# FISHFEEDER.net
KiCad netlist of a schematic drawn in EAGLE
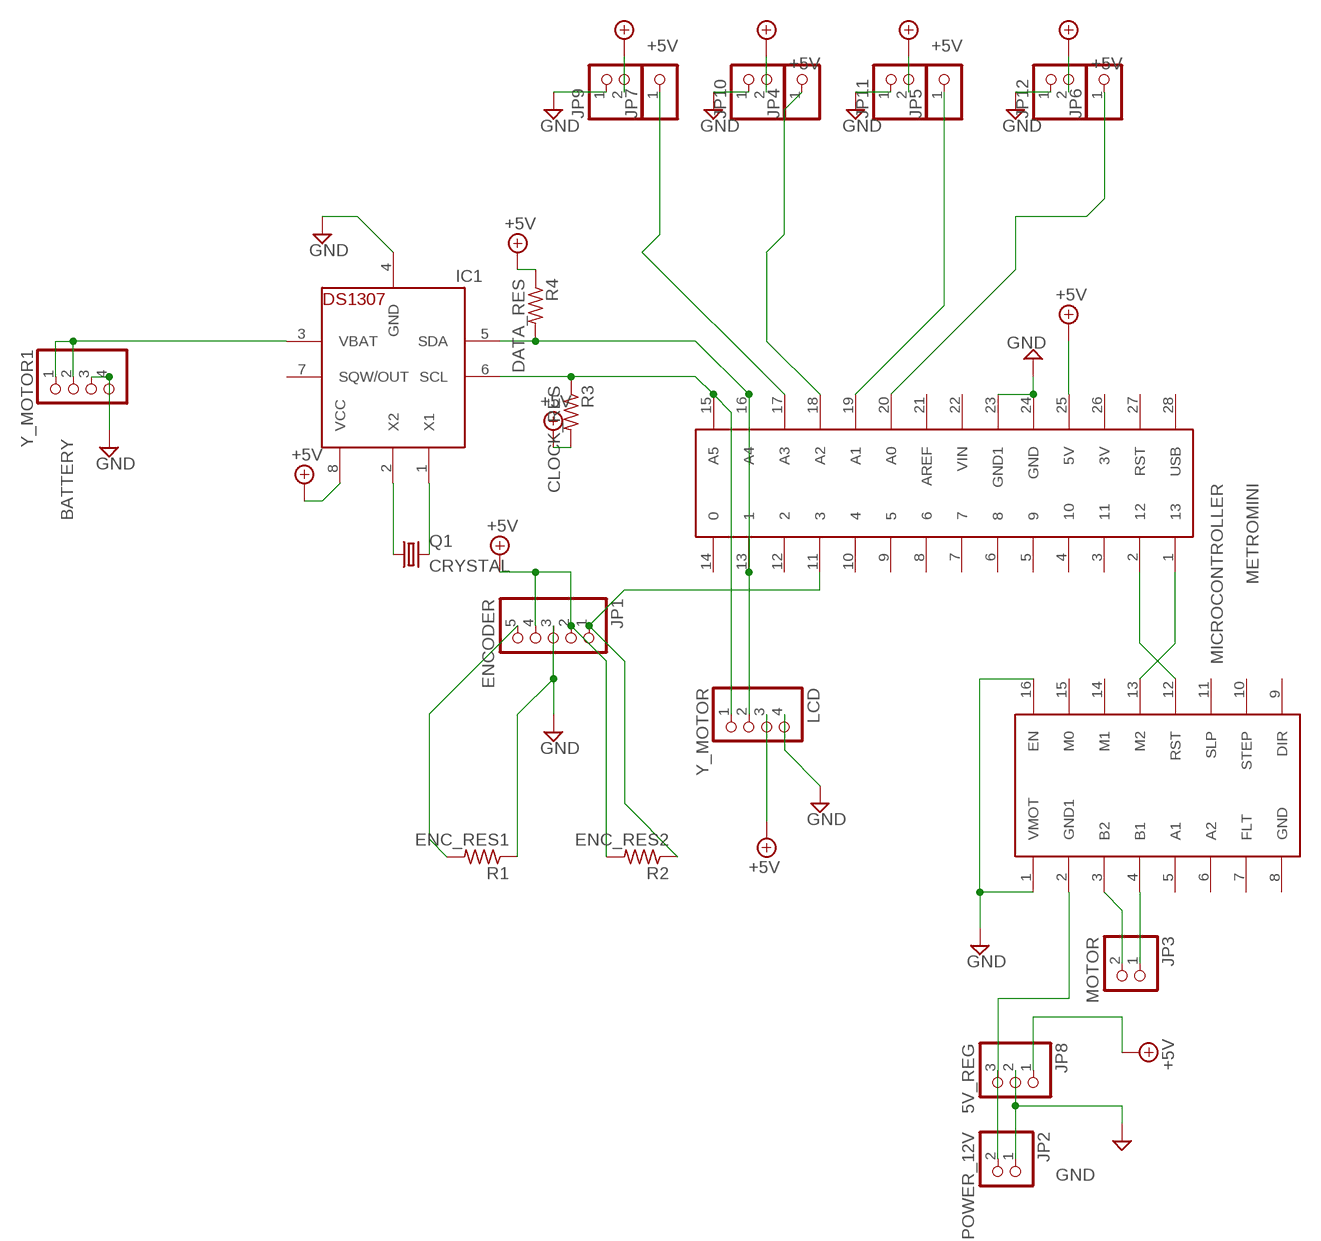
[diagram p0: schematic, sheet 1]

(export (version "E")
  (design (tool "Eeschema 10.0.6"))
  (components
    (comp (ref "IC1")
      (value "CLOCK_CHIP")
      (footprint "eagle-import:DIL08")
      (libsource (lib "eagle-import") (part "DS1307"))
    )
    (comp (ref "JP1")
      (value "ENCODER")
      (footprint "eagle-import:1X05")
      (libsource (lib "eagle-import") (part "PINHD-1X5"))
    )
    (comp (ref "JP2")
      (value "POWER_12V")
      (footprint "eagle-import:1X02")
      (libsource (lib "eagle-import") (part "PINHD-1X2"))
    )
    (comp (ref "JP3")
      (value "MOTOR")
      (footprint "eagle-import:1X02")
      (libsource (lib "eagle-import") (part "PINHD-1X2"))
    )
    (comp (ref "JP4")
      (value "PINHD-1X1CB")
      (footprint "eagle-import:1X01-CLEANBIG")
      (libsource (lib "eagle-import") (part "PINHD-1X1CB"))
    )
    (comp (ref "JP5")
      (value "PINHD-1X1CB")
      (footprint "eagle-import:1X01-CLEANBIG")
      (libsource (lib "eagle-import") (part "PINHD-1X1CB"))
    )
    (comp (ref "JP6")
      (value "PINHD-1X1CB")
      (footprint "eagle-import:1X01-CLEANBIG")
      (libsource (lib "eagle-import") (part "PINHD-1X1CB"))
    )
    (comp (ref "JP7")
      (value "PINHD-1X1CB")
      (footprint "eagle-import:1X01-CLEANBIG")
      (libsource (lib "eagle-import") (part "PINHD-1X1CB"))
    )
    (comp (ref "JP8")
      (value "5V_REG")
      (footprint "eagle-import:1X03")
      (libsource (lib "eagle-import") (part "PINHD-1X3"))
    )
    (comp (ref "JP9")
      (value "PINHD-1X2")
      (footprint "eagle-import:1X02")
      (libsource (lib "eagle-import") (part "PINHD-1X2"))
    )
    (comp (ref "JP10")
      (value "PINHD-1X2")
      (footprint "eagle-import:1X02")
      (libsource (lib "eagle-import") (part "PINHD-1X2"))
    )
    (comp (ref "JP11")
      (value "PINHD-1X2")
      (footprint "eagle-import:1X02")
      (libsource (lib "eagle-import") (part "PINHD-1X2"))
    )
    (comp (ref "JP12")
      (value "PINHD-1X2")
      (footprint "eagle-import:1X02")
      (libsource (lib "eagle-import") (part "PINHD-1X2"))
    )
    (comp (ref "MICROCONTROLLER")
      (value "METROMINI")
      (footprint "eagle-import:METROMINI")
      (libsource (lib "eagle-import") (part "METROMINI"))
    )
    (comp (ref "Q1")
      (value "CRYSTAL")
      (footprint "eagle-import:TC26H")
      (libsource (lib "eagle-import") (part "CRYSTALTC26H"))
    )
    (comp (ref "R1")
      (value "ENC_RES1")
      (footprint "eagle-import:0204_7")
      (libsource (lib "eagle-import") (part "R-US_0204/7"))
    )
    (comp (ref "R2")
      (value "ENC_RES2")
      (footprint "eagle-import:0204_7")
      (libsource (lib "eagle-import") (part "R-US_0204/7"))
    )
    (comp (ref "R3")
      (value "CLOCK_RES")
      (footprint "eagle-import:0204_7")
      (libsource (lib "eagle-import") (part "R-US_0204/7"))
    )
    (comp (ref "R4")
      (value "DATA_RES")
      (footprint "eagle-import:0204_7")
      (libsource (lib "eagle-import") (part "R-US_0204/7"))
    )
    (comp (ref "U$1")
      (value "DRV8825")
      (footprint "eagle-import:DRV8825")
      (libsource (lib "eagle-import") (part "DRV8825"))
    )
    (comp (ref "Y_MOTOR")
      (value "LCD")
      (footprint "eagle-import:1X04")
      (libsource (lib "eagle-import") (part "PINHD-1X4"))
    )
    (comp (ref "Y_MOTOR1")
      (value "BATTERY")
      (footprint "eagle-import:1X04")
      (libsource (lib "eagle-import") (part "PINHD-1X4"))
    )
  )
  (nets
    (net (code "1") (name "+5V") (class "Default")
      (node (ref "IC1") (pin "8") (pinfunction "VCC_8") (pintype "power_in"))
      (node (ref "JP1") (pin "2") (pinfunction "2_2") (pintype "passive"))
      (node (ref "JP1") (pin "4") (pinfunction "4_4") (pintype "passive"))
      (node (ref "JP10") (pin "2") (pinfunction "2_2") (pintype "passive"))
      (node (ref "JP11") (pin "2") (pinfunction "2_2") (pintype "passive"))
      (node (ref "JP12") (pin "2") (pinfunction "2_2") (pintype "passive"))
      (node (ref "JP8") (pin "1") (pinfunction "1_1") (pintype "passive"))
      (node (ref "JP9") (pin "2") (pinfunction "2_2") (pintype "passive"))
      (node (ref "MICROCONTROLLER") (pin "25") (pinfunction "5V_25") (pintype "bidirectional"))
      (node (ref "R2") (pin "2") (pinfunction "2_2") (pintype "passive"))
      (node (ref "R3") (pin "2") (pinfunction "2_2") (pintype "passive"))
      (node (ref "R4") (pin "1") (pinfunction "1_1") (pintype "passive"))
      (node (ref "Y_MOTOR") (pin "3") (pinfunction "3_3") (pintype "passive"))
    )
    (net (code "2") (name "GND") (class "Default")
      (node (ref "IC1") (pin "4") (pinfunction "GND_4") (pintype "power_in"))
      (node (ref "JP1") (pin "3") (pinfunction "3_3") (pintype "passive"))
      (node (ref "JP10") (pin "1") (pinfunction "1_1") (pintype "passive"))
      (node (ref "JP11") (pin "1") (pinfunction "1_1") (pintype "passive"))
      (node (ref "JP12") (pin "1") (pinfunction "1_1") (pintype "passive"))
      (node (ref "JP2") (pin "1") (pinfunction "1_1") (pintype "passive"))
      (node (ref "JP8") (pin "2") (pinfunction "2_2") (pintype "passive"))
      (node (ref "JP9") (pin "1") (pinfunction "1_1") (pintype "passive"))
      (node (ref "MICROCONTROLLER") (pin "23") (pinfunction "GND1_23") (pintype "bidirectional"))
      (node (ref "MICROCONTROLLER") (pin "24") (pinfunction "GND_24") (pintype "bidirectional"))
      (node (ref "R1") (pin "1") (pinfunction "1_1") (pintype "passive"))
      (node (ref "U$1") (pin "1") (pinfunction "VMOT_1") (pintype "bidirectional"))
      (node (ref "U$1") (pin "16") (pinfunction "EN_16") (pintype "bidirectional"))
      (node (ref "Y_MOTOR") (pin "4") (pinfunction "4_4") (pintype "passive"))
      (node (ref "Y_MOTOR1") (pin "3") (pinfunction "3_3") (pintype "passive"))
      (node (ref "Y_MOTOR1") (pin "4") (pinfunction "4_4") (pintype "passive"))
    )
    (net (code "3") (name "Net-(IC1-SCL)") (class "Default")
      (node (ref "IC1") (pin "6") (pinfunction "SCL_6") (pintype "bidirectional"))
      (node (ref "MICROCONTROLLER") (pin "15") (pinfunction "A5_15") (pintype "bidirectional"))
      (node (ref "R3") (pin "1") (pinfunction "1_1") (pintype "passive"))
      (node (ref "Y_MOTOR") (pin "1") (pinfunction "1_1") (pintype "passive"))
    )
    (net (code "4") (name "Net-(IC1-SDA)") (class "Default")
      (node (ref "IC1") (pin "5") (pinfunction "SDA_5") (pintype "bidirectional"))
      (node (ref "MICROCONTROLLER") (pin "13") (pinfunction "1_13") (pintype "bidirectional"))
      (node (ref "MICROCONTROLLER") (pin "16") (pinfunction "A4_16") (pintype "bidirectional"))
      (node (ref "R4") (pin "2") (pinfunction "2_2") (pintype "passive"))
      (node (ref "Y_MOTOR") (pin "2") (pinfunction "2_2") (pintype "passive"))
    )
    (net (code "5") (name "Net-(IC1-VBAT)") (class "Default")
      (node (ref "IC1") (pin "3") (pinfunction "VBAT_3") (pintype "power_in"))
      (node (ref "Y_MOTOR1") (pin "1") (pinfunction "1_1") (pintype "passive"))
      (node (ref "Y_MOTOR1") (pin "2") (pinfunction "2_2") (pintype "passive"))
    )
    (net (code "6") (name "Net-(IC1-X1)") (class "Default")
      (node (ref "IC1") (pin "1") (pinfunction "X1_1") (pintype "passive"))
      (node (ref "Q1") (pin "2") (pinfunction "2_2") (pintype "passive"))
    )
    (net (code "7") (name "Net-(IC1-X2)") (class "Default")
      (node (ref "IC1") (pin "2") (pinfunction "X2_2") (pintype "passive"))
      (node (ref "Q1") (pin "1") (pinfunction "1_1") (pintype "passive"))
    )
    (net (code "8") (name "Net-(JP1-Pad5)") (class "Default")
      (node (ref "JP1") (pin "5") (pinfunction "5_5") (pintype "passive"))
      (node (ref "R1") (pin "2") (pinfunction "2_2") (pintype "passive"))
    )
    (net (code "9") (name "Net-(MICROCONTROLLER-3)") (class "Default")
      (node (ref "JP1") (pin "1") (pinfunction "1_1") (pintype "passive"))
      (node (ref "MICROCONTROLLER") (pin "11") (pinfunction "3_11") (pintype "bidirectional"))
      (node (ref "R2") (pin "1") (pinfunction "1_1") (pintype "passive"))
    )
    (net (code "10") (name "Net-(MICROCONTROLLER-12)") (class "Default")
      (node (ref "MICROCONTROLLER") (pin "2") (pinfunction "12_2") (pintype "bidirectional"))
      (node (ref "U$1") (pin "12") (pinfunction "RST_12") (pintype "bidirectional"))
    )
    (net (code "11") (name "Net-(MICROCONTROLLER-13)") (class "Default")
      (node (ref "MICROCONTROLLER") (pin "1") (pinfunction "13_1") (pintype "bidirectional"))
      (node (ref "U$1") (pin "13") (pinfunction "M2_13") (pintype "bidirectional"))
    )
    (net (code "12") (name "Net-(MICROCONTROLLER-A0)") (class "Default")
      (node (ref "JP6") (pin "1") (pinfunction "1_1") (pintype "passive"))
      (node (ref "MICROCONTROLLER") (pin "20") (pinfunction "A0_20") (pintype "bidirectional"))
    )
    (net (code "13") (name "Net-(MICROCONTROLLER-A1)") (class "Default")
      (node (ref "JP5") (pin "1") (pinfunction "1_1") (pintype "passive"))
      (node (ref "MICROCONTROLLER") (pin "19") (pinfunction "A1_19") (pintype "bidirectional"))
    )
    (net (code "14") (name "Net-(MICROCONTROLLER-A2)") (class "Default")
      (node (ref "JP4") (pin "1") (pinfunction "1_1") (pintype "passive"))
      (node (ref "MICROCONTROLLER") (pin "18") (pinfunction "A2_18") (pintype "bidirectional"))
    )
    (net (code "15") (name "Net-(MICROCONTROLLER-A3)") (class "Default")
      (node (ref "JP7") (pin "1") (pinfunction "1_1") (pintype "passive"))
      (node (ref "MICROCONTROLLER") (pin "17") (pinfunction "A3_17") (pintype "bidirectional"))
    )
    (net (code "16") (name "Net-(U$1-B1)") (class "Default")
      (node (ref "JP3") (pin "1") (pinfunction "1_1") (pintype "passive"))
      (node (ref "U$1") (pin "4") (pinfunction "B1_4") (pintype "bidirectional"))
    )
    (net (code "17") (name "Net-(U$1-B2)") (class "Default")
      (node (ref "JP3") (pin "2") (pinfunction "2_2") (pintype "passive"))
      (node (ref "U$1") (pin "3") (pinfunction "B2_3") (pintype "bidirectional"))
    )
    (net (code "18") (name "Net-(U$1-GND1)") (class "Default")
      (node (ref "JP2") (pin "2") (pinfunction "2_2") (pintype "passive"))
      (node (ref "JP8") (pin "3") (pinfunction "3_3") (pintype "passive"))
      (node (ref "U$1") (pin "2") (pinfunction "GND1_2") (pintype "bidirectional"))
    )
    (net (code "19") (name "unconnected-(IC1-SQW{slash}OUT-Pad7)") (class "Default")
      (node (ref "IC1") (pin "7") (pinfunction "SQW/OUT_7") (pintype "bidirectional"))
    )
    (net (code "20") (name "unconnected-(MICROCONTROLLER-0-Pad14)") (class "Default")
      (node (ref "MICROCONTROLLER") (pin "14") (pinfunction "0_14") (pintype "bidirectional"))
    )
    (net (code "21") (name "unconnected-(MICROCONTROLLER-2-Pad12)") (class "Default")
      (node (ref "MICROCONTROLLER") (pin "12") (pinfunction "2_12") (pintype "bidirectional"))
    )
    (net (code "22") (name "unconnected-(MICROCONTROLLER-3V-Pad26)") (class "Default")
      (node (ref "MICROCONTROLLER") (pin "26") (pinfunction "3V_26") (pintype "bidirectional"))
    )
    (net (code "23") (name "unconnected-(MICROCONTROLLER-4-Pad10)") (class "Default")
      (node (ref "MICROCONTROLLER") (pin "10") (pinfunction "4_10") (pintype "bidirectional"))
    )
    (net (code "24") (name "unconnected-(MICROCONTROLLER-5-Pad9)") (class "Default")
      (node (ref "MICROCONTROLLER") (pin "9") (pinfunction "5_9") (pintype "bidirectional"))
    )
    (net (code "25") (name "unconnected-(MICROCONTROLLER-6-Pad8)") (class "Default")
      (node (ref "MICROCONTROLLER") (pin "8") (pinfunction "6_8") (pintype "bidirectional"))
    )
    (net (code "26") (name "unconnected-(MICROCONTROLLER-8-Pad6)") (class "Default")
      (node (ref "MICROCONTROLLER") (pin "6") (pinfunction "8_6") (pintype "bidirectional"))
    )
    (net (code "27") (name "unconnected-(MICROCONTROLLER-9-Pad5)") (class "Default")
      (node (ref "MICROCONTROLLER") (pin "5") (pinfunction "9_5") (pintype "bidirectional"))
    )
    (net (code "28") (name "unconnected-(MICROCONTROLLER-10-Pad4)") (class "Default")
      (node (ref "MICROCONTROLLER") (pin "4") (pinfunction "10_4") (pintype "bidirectional"))
    )
    (net (code "29") (name "unconnected-(MICROCONTROLLER-11-Pad3)") (class "Default")
      (node (ref "MICROCONTROLLER") (pin "3") (pinfunction "11_3") (pintype "bidirectional"))
    )
    (net (code "30") (name "unconnected-(MICROCONTROLLER-AREF-Pad21)") (class "Default")
      (node (ref "MICROCONTROLLER") (pin "21") (pinfunction "AREF_21") (pintype "bidirectional"))
    )
    (net (code "31") (name "unconnected-(MICROCONTROLLER-Pad7)") (class "Default")
      (node (ref "MICROCONTROLLER") (pin "7") (pinfunction "7_7") (pintype "bidirectional"))
    )
    (net (code "32") (name "unconnected-(MICROCONTROLLER-RST-Pad27)") (class "Default")
      (node (ref "MICROCONTROLLER") (pin "27") (pinfunction "RST_27") (pintype "bidirectional"))
    )
    (net (code "33") (name "unconnected-(MICROCONTROLLER-USB-Pad28)") (class "Default")
      (node (ref "MICROCONTROLLER") (pin "28") (pinfunction "USB_28") (pintype "bidirectional"))
    )
    (net (code "34") (name "unconnected-(MICROCONTROLLER-VIN-Pad22)") (class "Default")
      (node (ref "MICROCONTROLLER") (pin "22") (pinfunction "VIN_22") (pintype "bidirectional"))
    )
    (net (code "35") (name "unconnected-(U$1-A1-Pad5)") (class "Default")
      (node (ref "U$1") (pin "5") (pinfunction "A1_5") (pintype "bidirectional"))
    )
    (net (code "36") (name "unconnected-(U$1-A2-Pad6)") (class "Default")
      (node (ref "U$1") (pin "6") (pinfunction "A2_6") (pintype "bidirectional"))
    )
    (net (code "37") (name "unconnected-(U$1-DIR-Pad9)") (class "Default")
      (node (ref "U$1") (pin "9") (pinfunction "DIR_9") (pintype "bidirectional"))
    )
    (net (code "38") (name "unconnected-(U$1-FLT-Pad7)") (class "Default")
      (node (ref "U$1") (pin "7") (pinfunction "FLT_7") (pintype "bidirectional"))
    )
    (net (code "39") (name "unconnected-(U$1-GND-Pad8)") (class "Default")
      (node (ref "U$1") (pin "8") (pinfunction "GND_8") (pintype "bidirectional"))
    )
    (net (code "40") (name "unconnected-(U$1-M0-Pad15)") (class "Default")
      (node (ref "U$1") (pin "15") (pinfunction "M0_15") (pintype "bidirectional"))
    )
    (net (code "41") (name "unconnected-(U$1-M1-Pad14)") (class "Default")
      (node (ref "U$1") (pin "14") (pinfunction "M1_14") (pintype "bidirectional"))
    )
    (net (code "42") (name "unconnected-(U$1-SLP-Pad11)") (class "Default")
      (node (ref "U$1") (pin "11") (pinfunction "SLP_11") (pintype "bidirectional"))
    )
    (net (code "43") (name "unconnected-(U$1-STEP-Pad10)") (class "Default")
      (node (ref "U$1") (pin "10") (pinfunction "STEP_10") (pintype "bidirectional"))
    )
  )
)
